# Leistungsstufe.net
KiCad netlist of a schematic drawn in EAGLE
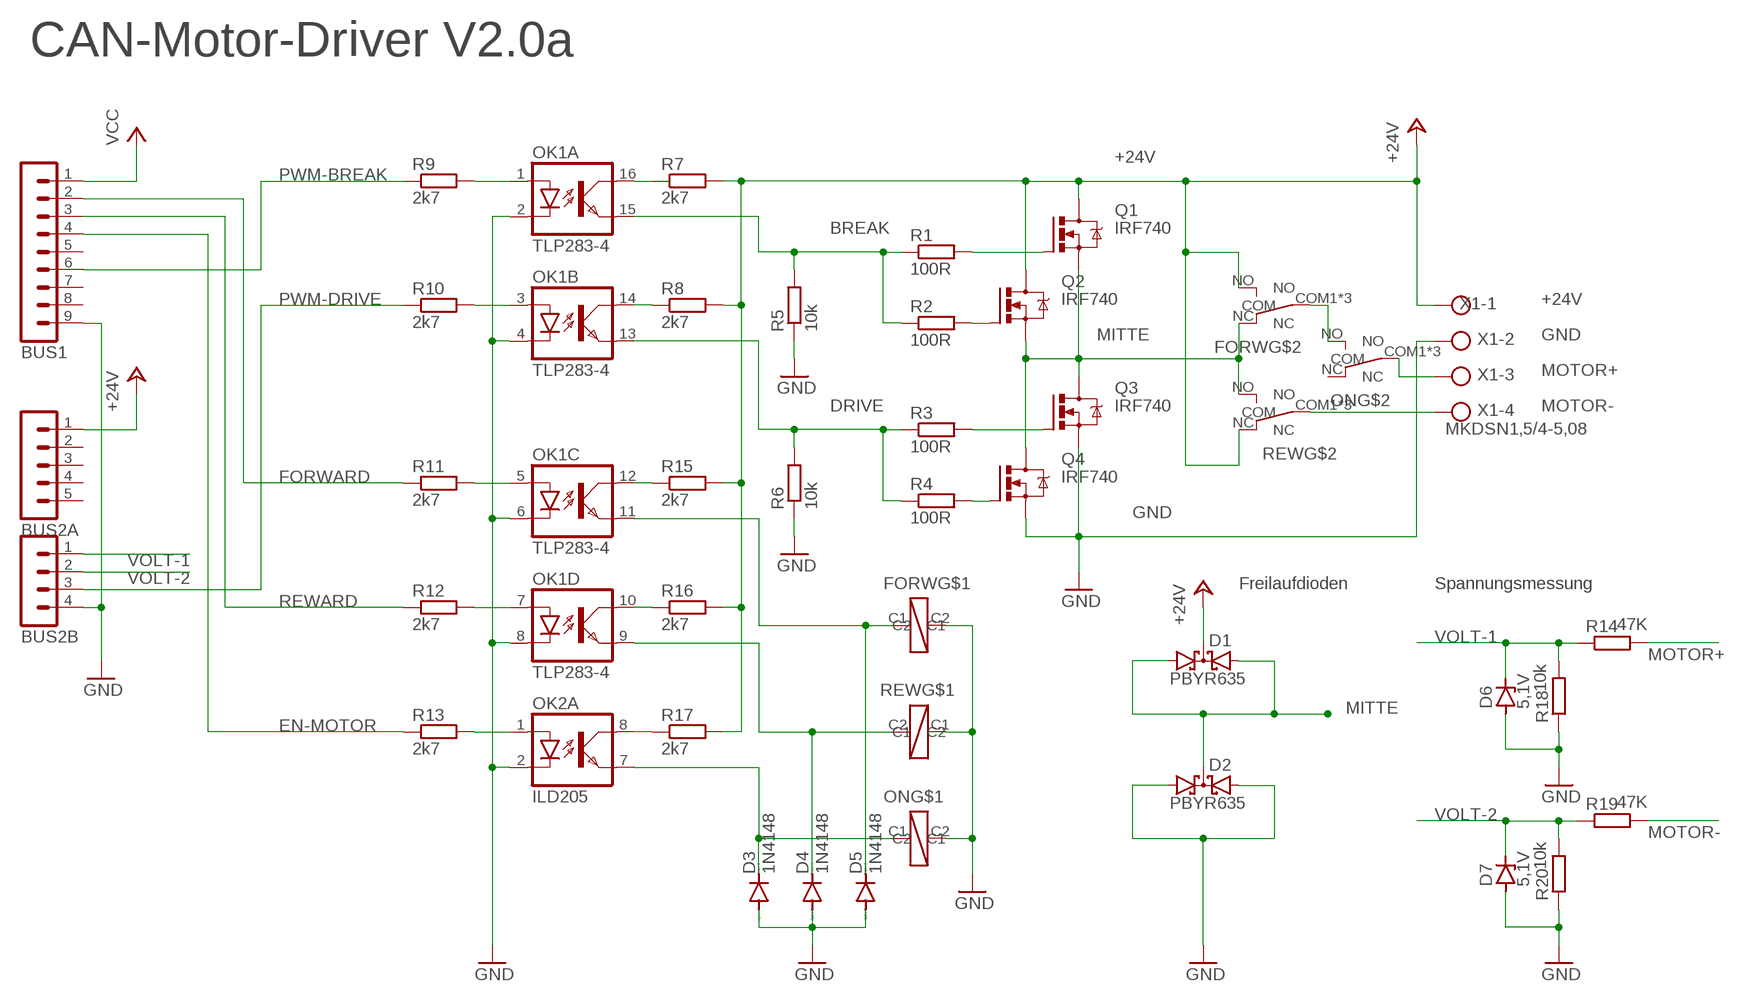
[diagram p0: schematic, sheet 1]

(export (version "E")
  (design (tool "Eeschema 10.0.6"))
  (components
    (comp (ref "BUS1")
      (value "MA09-1")
      (footprint "eagle-import:MA09-1")
      (libsource (lib "eagle-import") (part "MA09-1"))
    )
    (comp (ref "BUS2A")
      (value "MA05-1")
      (footprint "eagle-import:MA05-1")
      (libsource (lib "eagle-import") (part "MA05-1"))
    )
    (comp (ref "BUS2B")
      (value "MA04-1")
      (footprint "eagle-import:MA04-1")
      (libsource (lib "eagle-import") (part "MA04-1"))
    )
    (comp (ref "D1")
      (value "PBYR635")
      (footprint "eagle-import:SOT82S")
      (libsource (lib "eagle-import") (part "PBYR635"))
    )
    (comp (ref "D2")
      (value "PBYR635")
      (footprint "eagle-import:SOT82S")
      (libsource (lib "eagle-import") (part "PBYR635"))
    )
    (comp (ref "D3")
      (value "1N4148")
      (footprint "eagle-import:SOD323-R")
      (libsource (lib "eagle-import") (part "DIODE-SOD323-R"))
    )
    (comp (ref "D4")
      (value "1N4148")
      (footprint "eagle-import:SOD323-R")
      (libsource (lib "eagle-import") (part "DIODE-SOD323-R"))
    )
    (comp (ref "D5")
      (value "1N4148")
      (footprint "eagle-import:SOD323-R")
      (libsource (lib "eagle-import") (part "DIODE-SOD323-R"))
    )
    (comp (ref "D6")
      (value "5,1V")
      (footprint "eagle-import:SOD80C")
      (libsource (lib "eagle-import") (part "ZENER-DIODESOD80C"))
    )
    (comp (ref "D7")
      (value "5,1V")
      (footprint "eagle-import:SOD80C")
      (libsource (lib "eagle-import") (part "ZENER-DIODESOD80C"))
    )
    (comp (ref "FORW")
      (value "FRA2C-2")
      (footprint "eagle-import:FRA2C-2")
      (libsource (lib "eagle-import") (part "FRA2C-2"))
    )
    (comp (ref "OK1")
      (value "TLP283-4")
      (footprint "eagle-import:MINI-FLAT-16")
      (libsource (lib "eagle-import") (part "TLP283-4"))
    )
    (comp (ref "OK2")
      (value "ILD205")
      (footprint "eagle-import:SOIC08")
      (fields (field (name "MF") "VISHAY/TELEFUNKEN") (field (name "MPN") "ILD205T"))
      (libsource (lib "eagle-import") (part "ILD205"))
    )
    (comp (ref "ON")
      (value "FRA2C-2")
      (footprint "eagle-import:FRA2C-2")
      (libsource (lib "eagle-import") (part "FRA2C-2"))
    )
    (comp (ref "Q1")
      (value "IRF740")
      (footprint "eagle-import:TO220BV")
      (libsource (lib "eagle-import") (part "IRF740"))
    )
    (comp (ref "Q2")
      (value "IRF740")
      (footprint "eagle-import:TO220BV")
      (libsource (lib "eagle-import") (part "IRF740"))
    )
    (comp (ref "Q3")
      (value "IRF740")
      (footprint "eagle-import:TO220BV")
      (libsource (lib "eagle-import") (part "IRF740"))
    )
    (comp (ref "Q4")
      (value "IRF740")
      (footprint "eagle-import:TO220BV")
      (libsource (lib "eagle-import") (part "IRF740"))
    )
    (comp (ref "R1")
      (value "100R")
      (footprint "eagle-import:R0805")
      (libsource (lib "eagle-import") (part "R-EU_R0805"))
    )
    (comp (ref "R2")
      (value "100R")
      (footprint "eagle-import:R0805")
      (libsource (lib "eagle-import") (part "R-EU_R0805"))
    )
    (comp (ref "R3")
      (value "100R")
      (footprint "eagle-import:R0805")
      (libsource (lib "eagle-import") (part "R-EU_R0805"))
    )
    (comp (ref "R4")
      (value "100R")
      (footprint "eagle-import:R0805")
      (libsource (lib "eagle-import") (part "R-EU_R0805"))
    )
    (comp (ref "R5")
      (value "10k")
      (footprint "eagle-import:R0805")
      (libsource (lib "eagle-import") (part "R-EU_R0805"))
    )
    (comp (ref "R6")
      (value "10k")
      (footprint "eagle-import:R0805")
      (libsource (lib "eagle-import") (part "R-EU_R0805"))
    )
    (comp (ref "R7")
      (value "2k7")
      (footprint "eagle-import:R0805")
      (libsource (lib "eagle-import") (part "R-EU_R0805"))
    )
    (comp (ref "R8")
      (value "2k7")
      (footprint "eagle-import:R0805")
      (libsource (lib "eagle-import") (part "R-EU_R0805"))
    )
    (comp (ref "R9")
      (value "2k7")
      (footprint "eagle-import:R0805")
      (libsource (lib "eagle-import") (part "R-EU_R0805"))
    )
    (comp (ref "R10")
      (value "2k7")
      (footprint "eagle-import:R0805")
      (libsource (lib "eagle-import") (part "R-EU_R0805"))
    )
    (comp (ref "R11")
      (value "2k7")
      (footprint "eagle-import:R0805")
      (libsource (lib "eagle-import") (part "R-EU_R0805"))
    )
    (comp (ref "R12")
      (value "2k7")
      (footprint "eagle-import:R0805")
      (libsource (lib "eagle-import") (part "R-EU_R0805"))
    )
    (comp (ref "R13")
      (value "2k7")
      (footprint "eagle-import:R0805")
      (libsource (lib "eagle-import") (part "R-EU_R0805"))
    )
    (comp (ref "R14")
      (value "47K")
      (footprint "eagle-import:MINI_MELF-0102W")
      (libsource (lib "eagle-import") (part "R-EU_MELF0102W"))
    )
    (comp (ref "R15")
      (value "2k7")
      (footprint "eagle-import:R0805")
      (libsource (lib "eagle-import") (part "R-EU_R0805"))
    )
    (comp (ref "R16")
      (value "2k7")
      (footprint "eagle-import:R0805")
      (libsource (lib "eagle-import") (part "R-EU_R0805"))
    )
    (comp (ref "R17")
      (value "2k7")
      (footprint "eagle-import:R0805")
      (libsource (lib "eagle-import") (part "R-EU_R0805"))
    )
    (comp (ref "R18")
      (value "10k")
      (footprint "eagle-import:MINI_MELF-0102W")
      (libsource (lib "eagle-import") (part "R-EU_MELF0102W"))
    )
    (comp (ref "R19")
      (value "47K")
      (footprint "eagle-import:MINI_MELF-0102W")
      (libsource (lib "eagle-import") (part "R-EU_MELF0102W"))
    )
    (comp (ref "R20")
      (value "10k")
      (footprint "eagle-import:MINI_MELF-0102W")
      (libsource (lib "eagle-import") (part "R-EU_MELF0102W"))
    )
    (comp (ref "REW")
      (value "FRA2C-2")
      (footprint "eagle-import:FRA2C-2")
      (libsource (lib "eagle-import") (part "FRA2C-2"))
    )
    (comp (ref "X1")
      (value "MKDSN1,5/4-5,08")
      (footprint "eagle-import:MKDSN1,5_4-5,08")
      (libsource (lib "eagle-import") (part "MKDSN1,5/4-5,08"))
    )
  )
  (nets
    (net (code "1") (name "+24V") (class "Default")
      (node (ref "BUS2A") (pin "1") (pinfunction "1_1") (pintype "passive"))
      (node (ref "D1") (pin "C") (pinfunction "C_C") (pintype "passive"))
      (node (ref "FORW") (pin "NO") (pinfunction "NO_NO") (pintype "bidirectional"))
      (node (ref "Q1") (pin "D") (pinfunction "D_D") (pintype "passive"))
      (node (ref "Q2") (pin "D") (pinfunction "D_D") (pintype "passive"))
      (node (ref "R15") (pin "2") (pinfunction "2_2") (pintype "passive"))
      (node (ref "R16") (pin "2") (pinfunction "2_2") (pintype "passive"))
      (node (ref "R17") (pin "2") (pinfunction "2_2") (pintype "passive"))
      (node (ref "R7") (pin "2") (pinfunction "2_2") (pintype "passive"))
      (node (ref "R8") (pin "2") (pinfunction "2_2") (pintype "passive"))
      (node (ref "REW") (pin "NC") (pinfunction "NC_NC") (pintype "bidirectional"))
      (node (ref "X1") (pin "1") (pinfunction "KL_1") (pintype "passive"))
    )
    (net (code "2") (name "/BREAK") (class "Default")
      (node (ref "OK1") (pin "15") (pinfunction "EMIT_15") (pintype "passive"))
      (node (ref "R1") (pin "1") (pinfunction "1_1") (pintype "passive"))
      (node (ref "R2") (pin "1") (pinfunction "1_1") (pintype "passive"))
      (node (ref "R5") (pin "2") (pinfunction "2_2") (pintype "passive"))
    )
    (net (code "3") (name "/DRIVE") (class "Default")
      (node (ref "OK1") (pin "13") (pinfunction "EMIT_13") (pintype "passive"))
      (node (ref "R3") (pin "1") (pinfunction "1_1") (pintype "passive"))
      (node (ref "R4") (pin "1") (pinfunction "1_1") (pintype "passive"))
      (node (ref "R6") (pin "2") (pinfunction "2_2") (pintype "passive"))
    )
    (net (code "4") (name "/EN-MOTOR") (class "Default")
      (node (ref "BUS1") (pin "4") (pinfunction "4_4") (pintype "passive"))
      (node (ref "R13") (pin "1") (pinfunction "1_1") (pintype "passive"))
    )
    (net (code "5") (name "/FORWARD") (class "Default")
      (node (ref "BUS1") (pin "2") (pinfunction "2_2") (pintype "passive"))
      (node (ref "R11") (pin "1") (pinfunction "1_1") (pintype "passive"))
    )
    (net (code "6") (name "/MITTE") (class "Default")
      (node (ref "D1") (pin "A1") (pinfunction "A1_A1") (pintype "passive"))
      (node (ref "D1") (pin "A2") (pinfunction "A2_A2") (pintype "passive"))
      (node (ref "D2") (pin "C") (pinfunction "C_C") (pintype "passive"))
      (node (ref "FORW") (pin "NC") (pinfunction "NC_NC") (pintype "bidirectional"))
      (node (ref "Q1") (pin "S") (pinfunction "S_S") (pintype "passive"))
      (node (ref "Q2") (pin "S") (pinfunction "S_S") (pintype "passive"))
      (node (ref "Q3") (pin "D") (pinfunction "D_D") (pintype "passive"))
      (node (ref "Q4") (pin "D") (pinfunction "D_D") (pintype "passive"))
      (node (ref "REW") (pin "NO") (pinfunction "NO_NO") (pintype "bidirectional"))
    )
    (net (code "7") (name "/MOTOR+") (class "Default")
      (node (ref "ON") (pin "COM1") (pinfunction "COM_COM1") (pintype "bidirectional"))
      (node (ref "ON") (pin "COM2") (pinfunction "COM_COM2") (pintype "bidirectional"))
      (node (ref "ON") (pin "COM3") (pinfunction "COM_COM3") (pintype "bidirectional"))
      (node (ref "R14") (pin "2") (pinfunction "2_2") (pintype "passive"))
      (node (ref "X1") (pin "3") (pinfunction "KL_3") (pintype "passive"))
    )
    (net (code "8") (name "/MOTOR-") (class "Default")
      (node (ref "R19") (pin "2") (pinfunction "2_2") (pintype "passive"))
      (node (ref "REW") (pin "COM1") (pinfunction "COM_COM1") (pintype "bidirectional"))
      (node (ref "REW") (pin "COM2") (pinfunction "COM_COM2") (pintype "bidirectional"))
      (node (ref "REW") (pin "COM3") (pinfunction "COM_COM3") (pintype "bidirectional"))
      (node (ref "X1") (pin "4") (pinfunction "KL_4") (pintype "passive"))
    )
    (net (code "9") (name "/PWM-BREAK") (class "Default")
      (node (ref "BUS1") (pin "6") (pinfunction "6_6") (pintype "passive"))
      (node (ref "R9") (pin "1") (pinfunction "1_1") (pintype "passive"))
    )
    (net (code "10") (name "/PWM-DRIVE") (class "Default")
      (node (ref "BUS2B") (pin "3") (pinfunction "3_3") (pintype "passive"))
      (node (ref "R10") (pin "1") (pinfunction "1_1") (pintype "passive"))
    )
    (net (code "11") (name "/REWARD") (class "Default")
      (node (ref "BUS1") (pin "3") (pinfunction "3_3") (pintype "passive"))
      (node (ref "R12") (pin "1") (pinfunction "1_1") (pintype "passive"))
    )
    (net (code "12") (name "/VOLT-1") (class "Default")
      (node (ref "BUS2B") (pin "1") (pinfunction "1_1") (pintype "passive"))
      (node (ref "D6") (pin "C") (pinfunction "C_C") (pintype "passive"))
      (node (ref "R14") (pin "1") (pinfunction "1_1") (pintype "passive"))
      (node (ref "R18") (pin "2") (pinfunction "2_2") (pintype "passive"))
    )
    (net (code "13") (name "/VOLT-2") (class "Default")
      (node (ref "BUS2B") (pin "2") (pinfunction "2_2") (pintype "passive"))
      (node (ref "D7") (pin "C") (pinfunction "C_C") (pintype "passive"))
      (node (ref "R19") (pin "1") (pinfunction "1_1") (pintype "passive"))
      (node (ref "R20") (pin "2") (pinfunction "2_2") (pintype "passive"))
    )
    (net (code "14") (name "GND") (class "Default")
      (node (ref "BUS1") (pin "9") (pinfunction "9_9") (pintype "passive"))
      (node (ref "BUS2B") (pin "4") (pinfunction "4_4") (pintype "passive"))
      (node (ref "D2") (pin "A1") (pinfunction "A1_A1") (pintype "passive"))
      (node (ref "D2") (pin "A2") (pinfunction "A2_A2") (pintype "passive"))
      (node (ref "D3") (pin "A") (pinfunction "A_A") (pintype "passive"))
      (node (ref "D4") (pin "A") (pinfunction "A_A") (pintype "passive"))
      (node (ref "D5") (pin "A") (pinfunction "A_A") (pintype "passive"))
      (node (ref "D6") (pin "A") (pinfunction "A_A") (pintype "passive"))
      (node (ref "D7") (pin "A") (pinfunction "A_A") (pintype "passive"))
      (node (ref "FORW") (pin "C2") (pinfunction "C2_C2") (pintype "bidirectional"))
      (node (ref "OK1") (pin "2") (pinfunction "C_2") (pintype "passive"))
      (node (ref "OK1") (pin "4") (pinfunction "C_4") (pintype "passive"))
      (node (ref "OK1") (pin "6") (pinfunction "C_6") (pintype "passive"))
      (node (ref "OK1") (pin "8") (pinfunction "C_8") (pintype "passive"))
      (node (ref "OK2") (pin "2") (pinfunction "C_2") (pintype "passive"))
      (node (ref "ON") (pin "C2") (pinfunction "C2_C2") (pintype "bidirectional"))
      (node (ref "Q3") (pin "S") (pinfunction "S_S") (pintype "passive"))
      (node (ref "Q4") (pin "S") (pinfunction "S_S") (pintype "passive"))
      (node (ref "R18") (pin "1") (pinfunction "1_1") (pintype "passive"))
      (node (ref "R20") (pin "1") (pinfunction "1_1") (pintype "passive"))
      (node (ref "R5") (pin "1") (pinfunction "1_1") (pintype "passive"))
      (node (ref "R6") (pin "1") (pinfunction "1_1") (pintype "passive"))
      (node (ref "REW") (pin "C1") (pinfunction "C1_C1") (pintype "bidirectional"))
      (node (ref "X1") (pin "2") (pinfunction "KL_2") (pintype "passive"))
    )
    (net (code "15") (name "Net-(FORWB-COM-PadCOM1)") (class "Default")
      (node (ref "FORW") (pin "COM1") (pinfunction "COM_COM1") (pintype "bidirectional"))
      (node (ref "FORW") (pin "COM2") (pinfunction "COM_COM2") (pintype "bidirectional"))
      (node (ref "FORW") (pin "COM3") (pinfunction "COM_COM3") (pintype "bidirectional"))
      (node (ref "ON") (pin "NO") (pinfunction "NO_NO") (pintype "bidirectional"))
    )
    (net (code "16") (name "Net-(OK1A-A)") (class "Default")
      (node (ref "OK1") (pin "1") (pinfunction "A_1") (pintype "passive"))
      (node (ref "R9") (pin "2") (pinfunction "2_2") (pintype "passive"))
    )
    (net (code "17") (name "Net-(OK1A-COL)") (class "Default")
      (node (ref "OK1") (pin "16") (pinfunction "COL_16") (pintype "passive"))
      (node (ref "R7") (pin "1") (pinfunction "1_1") (pintype "passive"))
    )
    (net (code "18") (name "Net-(OK1B-A)") (class "Default")
      (node (ref "OK1") (pin "3") (pinfunction "A_3") (pintype "passive"))
      (node (ref "R10") (pin "2") (pinfunction "2_2") (pintype "passive"))
    )
    (net (code "19") (name "Net-(OK1B-COL)") (class "Default")
      (node (ref "OK1") (pin "14") (pinfunction "COL_14") (pintype "passive"))
      (node (ref "R8") (pin "1") (pinfunction "1_1") (pintype "passive"))
    )
    (net (code "20") (name "Net-(OK1C-A)") (class "Default")
      (node (ref "OK1") (pin "5") (pinfunction "A_5") (pintype "passive"))
      (node (ref "R11") (pin "2") (pinfunction "2_2") (pintype "passive"))
    )
    (net (code "21") (name "Net-(OK1C-COL)") (class "Default")
      (node (ref "OK1") (pin "12") (pinfunction "COL_12") (pintype "passive"))
      (node (ref "R15") (pin "1") (pinfunction "1_1") (pintype "passive"))
    )
    (net (code "22") (name "Net-(OK1C-EMIT)") (class "Default")
      (node (ref "D5") (pin "C") (pinfunction "C_C") (pintype "passive"))
      (node (ref "FORW") (pin "C1") (pinfunction "C1_C1") (pintype "bidirectional"))
      (node (ref "OK1") (pin "11") (pinfunction "EMIT_11") (pintype "passive"))
    )
    (net (code "23") (name "Net-(OK1D-A)") (class "Default")
      (node (ref "OK1") (pin "7") (pinfunction "A_7") (pintype "passive"))
      (node (ref "R12") (pin "2") (pinfunction "2_2") (pintype "passive"))
    )
    (net (code "24") (name "Net-(OK1D-COL)") (class "Default")
      (node (ref "OK1") (pin "10") (pinfunction "COL_10") (pintype "passive"))
      (node (ref "R16") (pin "1") (pinfunction "1_1") (pintype "passive"))
    )
    (net (code "25") (name "Net-(OK1D-EMIT)") (class "Default")
      (node (ref "D4") (pin "C") (pinfunction "C_C") (pintype "passive"))
      (node (ref "OK1") (pin "9") (pinfunction "EMIT_9") (pintype "passive"))
      (node (ref "REW") (pin "C2") (pinfunction "C2_C2") (pintype "bidirectional"))
    )
    (net (code "26") (name "Net-(OK2A-A)") (class "Default")
      (node (ref "OK2") (pin "1") (pinfunction "A_1") (pintype "passive"))
      (node (ref "R13") (pin "2") (pinfunction "2_2") (pintype "passive"))
    )
    (net (code "27") (name "Net-(OK2A-COL)") (class "Default")
      (node (ref "OK2") (pin "8") (pinfunction "COL_8") (pintype "passive"))
      (node (ref "R17") (pin "1") (pinfunction "1_1") (pintype "passive"))
    )
    (net (code "28") (name "Net-(OK2A-EMIT)") (class "Default")
      (node (ref "D3") (pin "C") (pinfunction "C_C") (pintype "passive"))
      (node (ref "OK2") (pin "7") (pinfunction "EMIT_7") (pintype "passive"))
      (node (ref "ON") (pin "C1") (pinfunction "C1_C1") (pintype "bidirectional"))
    )
    (net (code "29") (name "Net-(Q1-PadG)") (class "Default")
      (node (ref "Q1") (pin "G") (pinfunction "G_G") (pintype "passive"))
      (node (ref "R1") (pin "2") (pinfunction "2_2") (pintype "passive"))
    )
    (net (code "30") (name "Net-(Q2-PadG)") (class "Default")
      (node (ref "Q2") (pin "G") (pinfunction "G_G") (pintype "passive"))
      (node (ref "R2") (pin "2") (pinfunction "2_2") (pintype "passive"))
    )
    (net (code "31") (name "Net-(Q3-PadG)") (class "Default")
      (node (ref "Q3") (pin "G") (pinfunction "G_G") (pintype "passive"))
      (node (ref "R3") (pin "2") (pinfunction "2_2") (pintype "passive"))
    )
    (net (code "32") (name "Net-(Q4-PadG)") (class "Default")
      (node (ref "Q4") (pin "G") (pinfunction "G_G") (pintype "passive"))
      (node (ref "R4") (pin "2") (pinfunction "2_2") (pintype "passive"))
    )
    (net (code "33") (name "VCC") (class "Default")
      (node (ref "BUS1") (pin "1") (pinfunction "1_1") (pintype "passive"))
    )
    (net (code "34") (name "unconnected-(BUS1-Pad5)") (class "Default")
      (node (ref "BUS1") (pin "5") (pinfunction "5_5") (pintype "passive"))
    )
    (net (code "35") (name "unconnected-(BUS1-Pad7)") (class "Default")
      (node (ref "BUS1") (pin "7") (pinfunction "7_7") (pintype "passive"))
    )
    (net (code "36") (name "unconnected-(BUS1-Pad8)") (class "Default")
      (node (ref "BUS1") (pin "8") (pinfunction "8_8") (pintype "passive"))
    )
    (net (code "37") (name "unconnected-(BUS2A-Pad2)") (class "Default")
      (node (ref "BUS2A") (pin "2") (pinfunction "2_2") (pintype "passive"))
    )
    (net (code "38") (name "unconnected-(BUS2A-Pad3)") (class "Default")
      (node (ref "BUS2A") (pin "3") (pinfunction "3_3") (pintype "passive"))
    )
    (net (code "39") (name "unconnected-(BUS2A-Pad4)") (class "Default")
      (node (ref "BUS2A") (pin "4") (pinfunction "4_4") (pintype "passive"))
    )
    (net (code "40") (name "unconnected-(BUS2A-Pad5)") (class "Default")
      (node (ref "BUS2A") (pin "5") (pinfunction "5_5") (pintype "passive"))
    )
    (net (code "41") (name "unconnected-(ON-PadNC)") (class "Default")
      (node (ref "ON") (pin "NC") (pinfunction "NC_NC") (pintype "bidirectional"))
    )
  )
)
